# PGTNX01_teensy.net
KiCad netlist of a schematic drawn in EAGLE
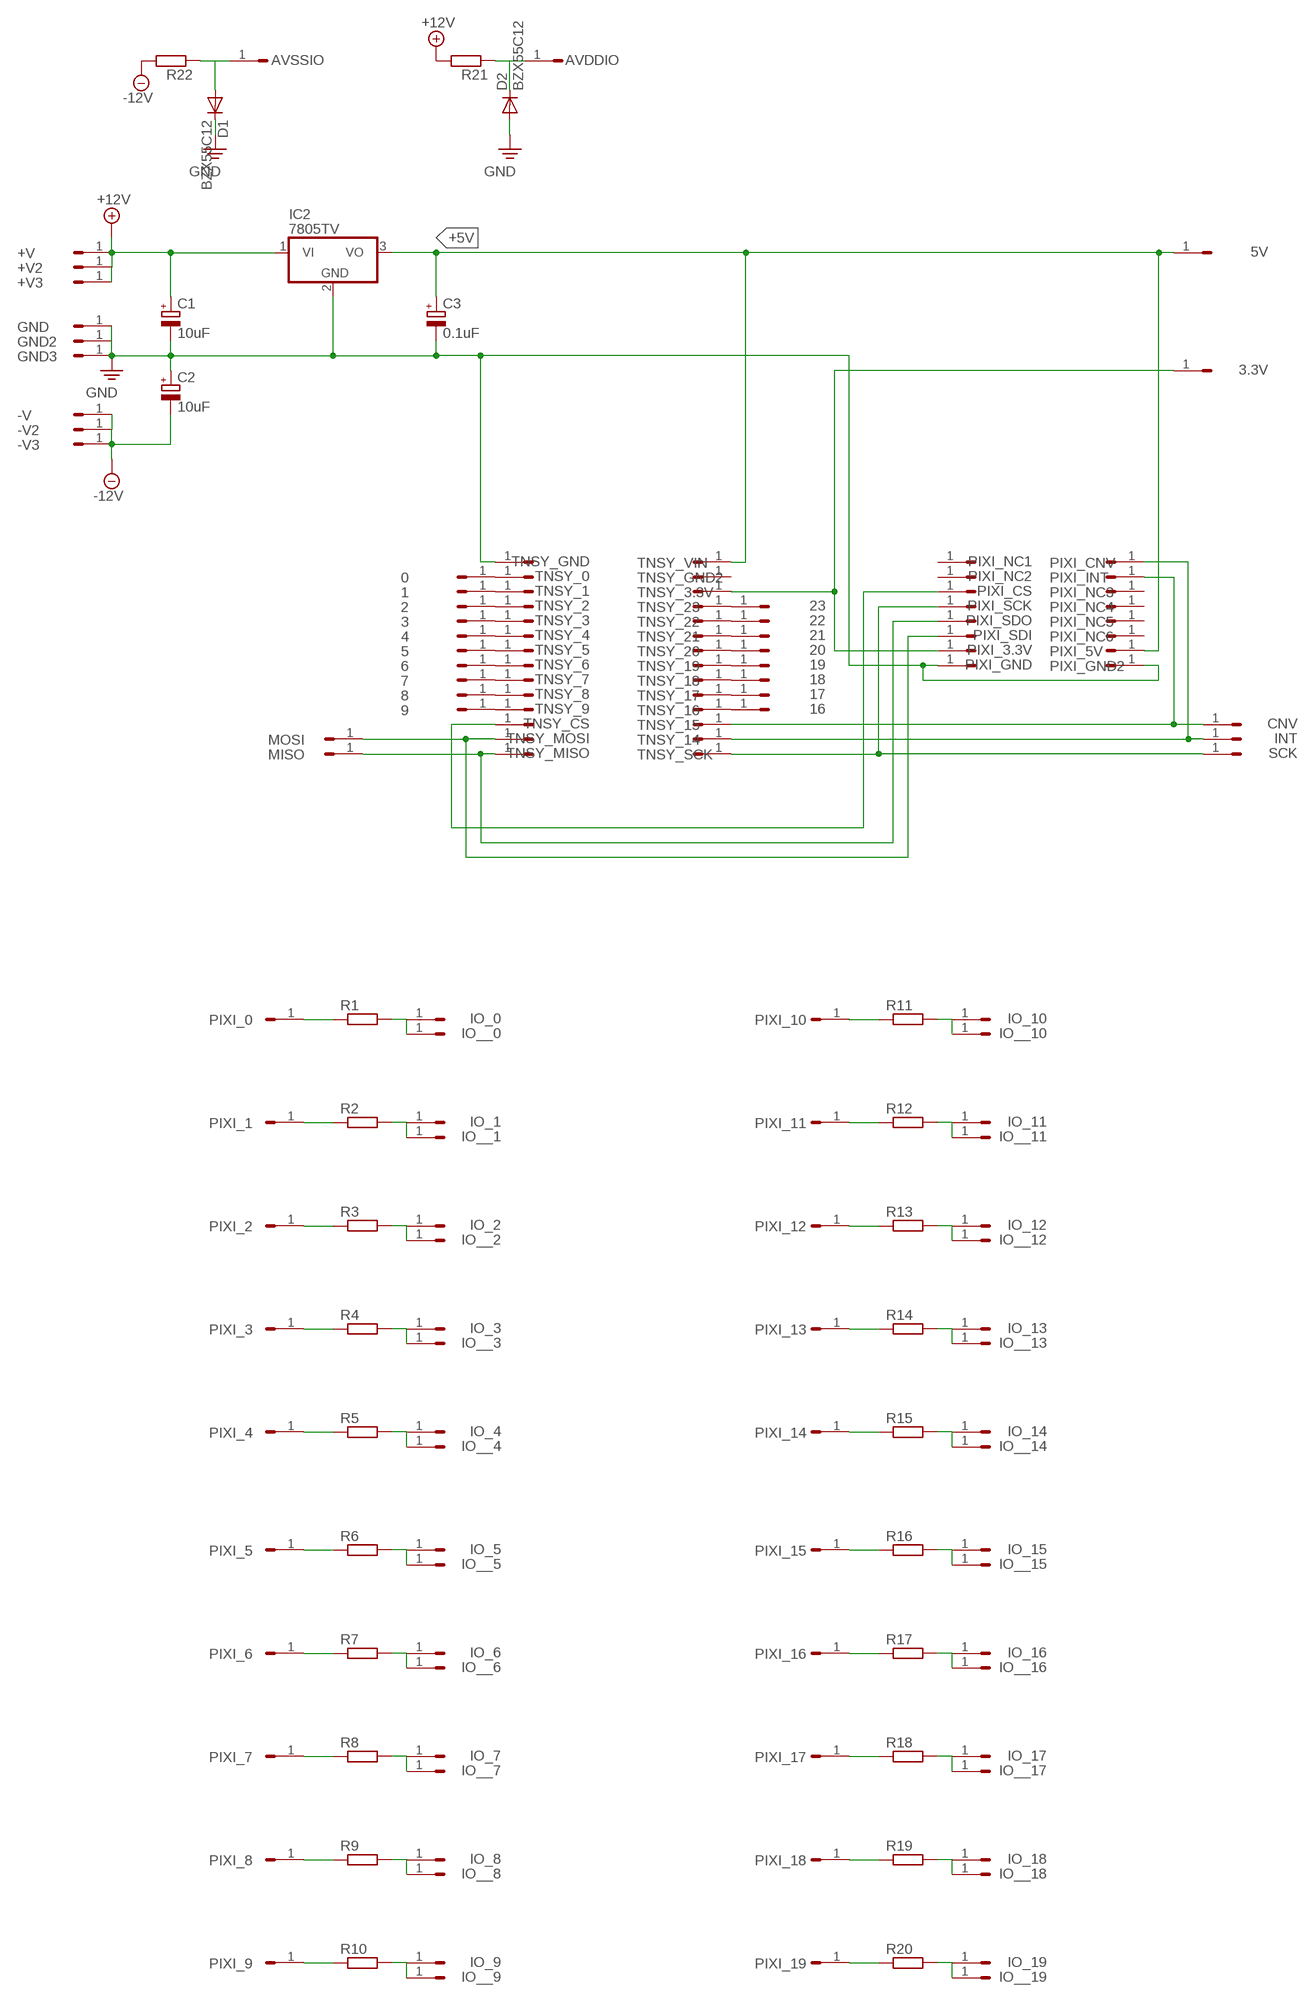
[diagram p0: schematic, sheet 1]

(export (version "E")
  (design (tool "Eeschema 10.0.6"))
  (components
    (comp (ref "+V")
      (value "HEADER/MALE/01")
      (footprint "eagle-import:HEADER_MALE_01")
      (fields (field (name "SPICEPREFIX") "X"))
      (libsource (lib "eagle-import") (part "HEADER/MALE/01"))
    )
    (comp (ref "+V2")
      (value "HEADER/MALE/01")
      (footprint "eagle-import:HEADER_MALE_01")
      (fields (field (name "SPICEPREFIX") "X"))
      (libsource (lib "eagle-import") (part "HEADER/MALE/01"))
    )
    (comp (ref "+V3")
      (value "HEADER/MALE/01")
      (footprint "eagle-import:HEADER_MALE_01")
      (fields (field (name "SPICEPREFIX") "X"))
      (libsource (lib "eagle-import") (part "HEADER/MALE/01"))
    )
    (comp (ref "-V")
      (value "HEADER/MALE/01")
      (footprint "eagle-import:HEADER_MALE_01")
      (fields (field (name "SPICEPREFIX") "X"))
      (libsource (lib "eagle-import") (part "HEADER/MALE/01"))
    )
    (comp (ref "-V2")
      (value "HEADER/MALE/01")
      (footprint "eagle-import:HEADER_MALE_01")
      (fields (field (name "SPICEPREFIX") "X"))
      (libsource (lib "eagle-import") (part "HEADER/MALE/01"))
    )
    (comp (ref "-V3")
      (value "HEADER/MALE/01")
      (footprint "eagle-import:HEADER_MALE_01")
      (fields (field (name "SPICEPREFIX") "X"))
      (libsource (lib "eagle-import") (part "HEADER/MALE/01"))
    )
    (comp (ref "0")
      (value "HEADER/MALE/01")
      (footprint "eagle-import:HEADER_MALE_01")
      (fields (field (name "SPICEPREFIX") "X"))
      (libsource (lib "eagle-import") (part "HEADER/MALE/01"))
    )
    (comp (ref "1")
      (value "HEADER/MALE/01")
      (footprint "eagle-import:HEADER_MALE_01")
      (fields (field (name "SPICEPREFIX") "X"))
      (libsource (lib "eagle-import") (part "HEADER/MALE/01"))
    )
    (comp (ref "2")
      (value "HEADER/MALE/01")
      (footprint "eagle-import:HEADER_MALE_01")
      (fields (field (name "SPICEPREFIX") "X"))
      (libsource (lib "eagle-import") (part "HEADER/MALE/01"))
    )
    (comp (ref "3")
      (value "HEADER/MALE/01")
      (footprint "eagle-import:HEADER_MALE_01")
      (fields (field (name "SPICEPREFIX") "X"))
      (libsource (lib "eagle-import") (part "HEADER/MALE/01"))
    )
    (comp (ref "3.3V")
      (value "HEADER/MALE/01")
      (footprint "eagle-import:HEADER_MALE_01")
      (fields (field (name "SPICEPREFIX") "X"))
      (libsource (lib "eagle-import") (part "HEADER/MALE/01"))
    )
    (comp (ref "4")
      (value "HEADER/MALE/01")
      (footprint "eagle-import:HEADER_MALE_01")
      (fields (field (name "SPICEPREFIX") "X"))
      (libsource (lib "eagle-import") (part "HEADER/MALE/01"))
    )
    (comp (ref "5")
      (value "HEADER/MALE/01")
      (footprint "eagle-import:HEADER_MALE_01")
      (fields (field (name "SPICEPREFIX") "X"))
      (libsource (lib "eagle-import") (part "HEADER/MALE/01"))
    )
    (comp (ref "5V")
      (value "HEADER/MALE/01")
      (footprint "eagle-import:HEADER_MALE_01")
      (fields (field (name "SPICEPREFIX") "X"))
      (libsource (lib "eagle-import") (part "HEADER/MALE/01"))
    )
    (comp (ref "6")
      (value "HEADER/MALE/01")
      (footprint "eagle-import:HEADER_MALE_01")
      (fields (field (name "SPICEPREFIX") "X"))
      (libsource (lib "eagle-import") (part "HEADER/MALE/01"))
    )
    (comp (ref "7")
      (value "HEADER/MALE/01")
      (footprint "eagle-import:HEADER_MALE_01")
      (fields (field (name "SPICEPREFIX") "X"))
      (libsource (lib "eagle-import") (part "HEADER/MALE/01"))
    )
    (comp (ref "8")
      (value "HEADER/MALE/01")
      (footprint "eagle-import:HEADER_MALE_01")
      (fields (field (name "SPICEPREFIX") "X"))
      (libsource (lib "eagle-import") (part "HEADER/MALE/01"))
    )
    (comp (ref "9")
      (value "HEADER/MALE/01")
      (footprint "eagle-import:HEADER_MALE_01")
      (fields (field (name "SPICEPREFIX") "X"))
      (libsource (lib "eagle-import") (part "HEADER/MALE/01"))
    )
    (comp (ref "16")
      (value "HEADER/MALE/01")
      (footprint "eagle-import:HEADER_MALE_01")
      (fields (field (name "SPICEPREFIX") "X"))
      (libsource (lib "eagle-import") (part "HEADER/MALE/01"))
    )
    (comp (ref "17")
      (value "HEADER/MALE/01")
      (footprint "eagle-import:HEADER_MALE_01")
      (fields (field (name "SPICEPREFIX") "X"))
      (libsource (lib "eagle-import") (part "HEADER/MALE/01"))
    )
    (comp (ref "18")
      (value "HEADER/MALE/01")
      (footprint "eagle-import:HEADER_MALE_01")
      (fields (field (name "SPICEPREFIX") "X"))
      (libsource (lib "eagle-import") (part "HEADER/MALE/01"))
    )
    (comp (ref "19")
      (value "HEADER/MALE/01")
      (footprint "eagle-import:HEADER_MALE_01")
      (fields (field (name "SPICEPREFIX") "X"))
      (libsource (lib "eagle-import") (part "HEADER/MALE/01"))
    )
    (comp (ref "20")
      (value "HEADER/MALE/01")
      (footprint "eagle-import:HEADER_MALE_01")
      (fields (field (name "SPICEPREFIX") "X"))
      (libsource (lib "eagle-import") (part "HEADER/MALE/01"))
    )
    (comp (ref "21")
      (value "HEADER/MALE/01")
      (footprint "eagle-import:HEADER_MALE_01")
      (fields (field (name "SPICEPREFIX") "X"))
      (libsource (lib "eagle-import") (part "HEADER/MALE/01"))
    )
    (comp (ref "22")
      (value "HEADER/MALE/01")
      (footprint "eagle-import:HEADER_MALE_01")
      (fields (field (name "SPICEPREFIX") "X"))
      (libsource (lib "eagle-import") (part "HEADER/MALE/01"))
    )
    (comp (ref "23")
      (value "HEADER/MALE/01")
      (footprint "eagle-import:HEADER_MALE_01")
      (fields (field (name "SPICEPREFIX") "X"))
      (libsource (lib "eagle-import") (part "HEADER/MALE/01"))
    )
    (comp (ref "AVDDIO")
      (value "HEADER/MALE/01")
      (footprint "eagle-import:HEADER_MALE_01")
      (fields (field (name "SPICEPREFIX") "X"))
      (libsource (lib "eagle-import") (part "HEADER/MALE/01"))
    )
    (comp (ref "AVSSIO")
      (value "HEADER/MALE/01")
      (footprint "eagle-import:HEADER_MALE_01")
      (fields (field (name "SPICEPREFIX") "X"))
      (libsource (lib "eagle-import") (part "HEADER/MALE/01"))
    )
    (comp (ref "C1")
      (value "10uF")
      (footprint "eagle-import:E2,5-6")
      (fields (field (name "SPICEPREFIX") "C"))
      (libsource (lib "eagle-import") (part "CAPACITOR/POLARIZEDE2.5-6"))
    )
    (comp (ref "C2")
      (value "10uF")
      (footprint "eagle-import:E2,5-6")
      (fields (field (name "SPICEPREFIX") "C"))
      (libsource (lib "eagle-import") (part "CAPACITOR/POLARIZEDE2.5-6"))
    )
    (comp (ref "C3")
      (value "0.1uF")
      (footprint "eagle-import:E2,5-6")
      (fields (field (name "SPICEPREFIX") "C"))
      (libsource (lib "eagle-import") (part "CAPACITOR/POLARIZEDE2.5-6"))
    )
    (comp (ref "CNV")
      (value "HEADER/MALE/01")
      (footprint "eagle-import:HEADER_MALE_01")
      (fields (field (name "SPICEPREFIX") "X"))
      (libsource (lib "eagle-import") (part "HEADER/MALE/01"))
    )
    (comp (ref "D1")
      (value "BZX55C12")
      (footprint "eagle-import:DO35-7")
      (libsource (lib "eagle-import") (part "1N4148DO35-7"))
    )
    (comp (ref "D2")
      (value "BZX55C12")
      (footprint "eagle-import:DO35-7")
      (libsource (lib "eagle-import") (part "1N4148DO35-7"))
    )
    (comp (ref "GND")
      (value "HEADER/MALE/01")
      (footprint "eagle-import:HEADER_MALE_01")
      (fields (field (name "SPICEPREFIX") "X"))
      (libsource (lib "eagle-import") (part "HEADER/MALE/01"))
    )
    (comp (ref "GND2")
      (value "HEADER/MALE/01")
      (footprint "eagle-import:HEADER_MALE_01")
      (fields (field (name "SPICEPREFIX") "X"))
      (libsource (lib "eagle-import") (part "HEADER/MALE/01"))
    )
    (comp (ref "GND3")
      (value "HEADER/MALE/01")
      (footprint "eagle-import:HEADER_MALE_01")
      (fields (field (name "SPICEPREFIX") "X"))
      (libsource (lib "eagle-import") (part "HEADER/MALE/01"))
    )
    (comp (ref "IC2")
      (value "7805TV")
      (footprint "eagle-import:TO220V")
      (libsource (lib "eagle-import") (part "78TV05"))
    )
    (comp (ref "INT")
      (value "HEADER/MALE/01")
      (footprint "eagle-import:HEADER_MALE_01")
      (fields (field (name "SPICEPREFIX") "X"))
      (libsource (lib "eagle-import") (part "HEADER/MALE/01"))
    )
    (comp (ref "IO_0")
      (value "HEADER/MALE/01")
      (footprint "eagle-import:HEADER_MALE_01")
      (fields (field (name "SPICEPREFIX") "X"))
      (libsource (lib "eagle-import") (part "HEADER/MALE/01"))
    )
    (comp (ref "IO_1")
      (value "HEADER/MALE/01")
      (footprint "eagle-import:HEADER_MALE_01")
      (fields (field (name "SPICEPREFIX") "X"))
      (libsource (lib "eagle-import") (part "HEADER/MALE/01"))
    )
    (comp (ref "IO_2")
      (value "HEADER/MALE/01")
      (footprint "eagle-import:HEADER_MALE_01")
      (fields (field (name "SPICEPREFIX") "X"))
      (libsource (lib "eagle-import") (part "HEADER/MALE/01"))
    )
    (comp (ref "IO_3")
      (value "HEADER/MALE/01")
      (footprint "eagle-import:HEADER_MALE_01")
      (fields (field (name "SPICEPREFIX") "X"))
      (libsource (lib "eagle-import") (part "HEADER/MALE/01"))
    )
    (comp (ref "IO_4")
      (value "HEADER/MALE/01")
      (footprint "eagle-import:HEADER_MALE_01")
      (fields (field (name "SPICEPREFIX") "X"))
      (libsource (lib "eagle-import") (part "HEADER/MALE/01"))
    )
    (comp (ref "IO_5")
      (value "HEADER/MALE/01")
      (footprint "eagle-import:HEADER_MALE_01")
      (fields (field (name "SPICEPREFIX") "X"))
      (libsource (lib "eagle-import") (part "HEADER/MALE/01"))
    )
    (comp (ref "IO_6")
      (value "HEADER/MALE/01")
      (footprint "eagle-import:HEADER_MALE_01")
      (fields (field (name "SPICEPREFIX") "X"))
      (libsource (lib "eagle-import") (part "HEADER/MALE/01"))
    )
    (comp (ref "IO_7")
      (value "HEADER/MALE/01")
      (footprint "eagle-import:HEADER_MALE_01")
      (fields (field (name "SPICEPREFIX") "X"))
      (libsource (lib "eagle-import") (part "HEADER/MALE/01"))
    )
    (comp (ref "IO_8")
      (value "HEADER/MALE/01")
      (footprint "eagle-import:HEADER_MALE_01")
      (fields (field (name "SPICEPREFIX") "X"))
      (libsource (lib "eagle-import") (part "HEADER/MALE/01"))
    )
    (comp (ref "IO_9")
      (value "HEADER/MALE/01")
      (footprint "eagle-import:HEADER_MALE_01")
      (fields (field (name "SPICEPREFIX") "X"))
      (libsource (lib "eagle-import") (part "HEADER/MALE/01"))
    )
    (comp (ref "IO_10")
      (value "HEADER/MALE/01")
      (footprint "eagle-import:HEADER_MALE_01")
      (fields (field (name "SPICEPREFIX") "X"))
      (libsource (lib "eagle-import") (part "HEADER/MALE/01"))
    )
    (comp (ref "IO_11")
      (value "HEADER/MALE/01")
      (footprint "eagle-import:HEADER_MALE_01")
      (fields (field (name "SPICEPREFIX") "X"))
      (libsource (lib "eagle-import") (part "HEADER/MALE/01"))
    )
    (comp (ref "IO_12")
      (value "HEADER/MALE/01")
      (footprint "eagle-import:HEADER_MALE_01")
      (fields (field (name "SPICEPREFIX") "X"))
      (libsource (lib "eagle-import") (part "HEADER/MALE/01"))
    )
    (comp (ref "IO_13")
      (value "HEADER/MALE/01")
      (footprint "eagle-import:HEADER_MALE_01")
      (fields (field (name "SPICEPREFIX") "X"))
      (libsource (lib "eagle-import") (part "HEADER/MALE/01"))
    )
    (comp (ref "IO_14")
      (value "HEADER/MALE/01")
      (footprint "eagle-import:HEADER_MALE_01")
      (fields (field (name "SPICEPREFIX") "X"))
      (libsource (lib "eagle-import") (part "HEADER/MALE/01"))
    )
    (comp (ref "IO_15")
      (value "HEADER/MALE/01")
      (footprint "eagle-import:HEADER_MALE_01")
      (fields (field (name "SPICEPREFIX") "X"))
      (libsource (lib "eagle-import") (part "HEADER/MALE/01"))
    )
    (comp (ref "IO_16")
      (value "HEADER/MALE/01")
      (footprint "eagle-import:HEADER_MALE_01")
      (fields (field (name "SPICEPREFIX") "X"))
      (libsource (lib "eagle-import") (part "HEADER/MALE/01"))
    )
    (comp (ref "IO_17")
      (value "HEADER/MALE/01")
      (footprint "eagle-import:HEADER_MALE_01")
      (fields (field (name "SPICEPREFIX") "X"))
      (libsource (lib "eagle-import") (part "HEADER/MALE/01"))
    )
    (comp (ref "IO_18")
      (value "HEADER/MALE/01")
      (footprint "eagle-import:HEADER_MALE_01")
      (fields (field (name "SPICEPREFIX") "X"))
      (libsource (lib "eagle-import") (part "HEADER/MALE/01"))
    )
    (comp (ref "IO_19")
      (value "HEADER/MALE/01")
      (footprint "eagle-import:HEADER_MALE_01")
      (fields (field (name "SPICEPREFIX") "X"))
      (libsource (lib "eagle-import") (part "HEADER/MALE/01"))
    )
    (comp (ref "IO__0")
      (value "HEADER/MALE/01")
      (footprint "eagle-import:HEADER_MALE_01")
      (fields (field (name "SPICEPREFIX") "X"))
      (libsource (lib "eagle-import") (part "HEADER/MALE/01"))
    )
    (comp (ref "IO__1")
      (value "HEADER/MALE/01")
      (footprint "eagle-import:HEADER_MALE_01")
      (fields (field (name "SPICEPREFIX") "X"))
      (libsource (lib "eagle-import") (part "HEADER/MALE/01"))
    )
    (comp (ref "IO__2")
      (value "HEADER/MALE/01")
      (footprint "eagle-import:HEADER_MALE_01")
      (fields (field (name "SPICEPREFIX") "X"))
      (libsource (lib "eagle-import") (part "HEADER/MALE/01"))
    )
    (comp (ref "IO__3")
      (value "HEADER/MALE/01")
      (footprint "eagle-import:HEADER_MALE_01")
      (fields (field (name "SPICEPREFIX") "X"))
      (libsource (lib "eagle-import") (part "HEADER/MALE/01"))
    )
    (comp (ref "IO__4")
      (value "HEADER/MALE/01")
      (footprint "eagle-import:HEADER_MALE_01")
      (fields (field (name "SPICEPREFIX") "X"))
      (libsource (lib "eagle-import") (part "HEADER/MALE/01"))
    )
    (comp (ref "IO__5")
      (value "HEADER/MALE/01")
      (footprint "eagle-import:HEADER_MALE_01")
      (fields (field (name "SPICEPREFIX") "X"))
      (libsource (lib "eagle-import") (part "HEADER/MALE/01"))
    )
    (comp (ref "IO__6")
      (value "HEADER/MALE/01")
      (footprint "eagle-import:HEADER_MALE_01")
      (fields (field (name "SPICEPREFIX") "X"))
      (libsource (lib "eagle-import") (part "HEADER/MALE/01"))
    )
    (comp (ref "IO__7")
      (value "HEADER/MALE/01")
      (footprint "eagle-import:HEADER_MALE_01")
      (fields (field (name "SPICEPREFIX") "X"))
      (libsource (lib "eagle-import") (part "HEADER/MALE/01"))
    )
    (comp (ref "IO__8")
      (value "HEADER/MALE/01")
      (footprint "eagle-import:HEADER_MALE_01")
      (fields (field (name "SPICEPREFIX") "X"))
      (libsource (lib "eagle-import") (part "HEADER/MALE/01"))
    )
    (comp (ref "IO__9")
      (value "HEADER/MALE/01")
      (footprint "eagle-import:HEADER_MALE_01")
      (fields (field (name "SPICEPREFIX") "X"))
      (libsource (lib "eagle-import") (part "HEADER/MALE/01"))
    )
    (comp (ref "IO__10")
      (value "HEADER/MALE/01")
      (footprint "eagle-import:HEADER_MALE_01")
      (fields (field (name "SPICEPREFIX") "X"))
      (libsource (lib "eagle-import") (part "HEADER/MALE/01"))
    )
    (comp (ref "IO__11")
      (value "HEADER/MALE/01")
      (footprint "eagle-import:HEADER_MALE_01")
      (fields (field (name "SPICEPREFIX") "X"))
      (libsource (lib "eagle-import") (part "HEADER/MALE/01"))
    )
    (comp (ref "IO__12")
      (value "HEADER/MALE/01")
      (footprint "eagle-import:HEADER_MALE_01")
      (fields (field (name "SPICEPREFIX") "X"))
      (libsource (lib "eagle-import") (part "HEADER/MALE/01"))
    )
    (comp (ref "IO__13")
      (value "HEADER/MALE/01")
      (footprint "eagle-import:HEADER_MALE_01")
      (fields (field (name "SPICEPREFIX") "X"))
      (libsource (lib "eagle-import") (part "HEADER/MALE/01"))
    )
    (comp (ref "IO__14")
      (value "HEADER/MALE/01")
      (footprint "eagle-import:HEADER_MALE_01")
      (fields (field (name "SPICEPREFIX") "X"))
      (libsource (lib "eagle-import") (part "HEADER/MALE/01"))
    )
    (comp (ref "IO__15")
      (value "HEADER/MALE/01")
      (footprint "eagle-import:HEADER_MALE_01")
      (fields (field (name "SPICEPREFIX") "X"))
      (libsource (lib "eagle-import") (part "HEADER/MALE/01"))
    )
    (comp (ref "IO__16")
      (value "HEADER/MALE/01")
      (footprint "eagle-import:HEADER_MALE_01")
      (fields (field (name "SPICEPREFIX") "X"))
      (libsource (lib "eagle-import") (part "HEADER/MALE/01"))
    )
    (comp (ref "IO__17")
      (value "HEADER/MALE/01")
      (footprint "eagle-import:HEADER_MALE_01")
      (fields (field (name "SPICEPREFIX") "X"))
      (libsource (lib "eagle-import") (part "HEADER/MALE/01"))
    )
    (comp (ref "IO__18")
      (value "HEADER/MALE/01")
      (footprint "eagle-import:HEADER_MALE_01")
      (fields (field (name "SPICEPREFIX") "X"))
      (libsource (lib "eagle-import") (part "HEADER/MALE/01"))
    )
    (comp (ref "IO__19")
      (value "HEADER/MALE/01")
      (footprint "eagle-import:HEADER_MALE_01")
      (fields (field (name "SPICEPREFIX") "X"))
      (libsource (lib "eagle-import") (part "HEADER/MALE/01"))
    )
    (comp (ref "MISO")
      (value "HEADER/MALE/01")
      (footprint "eagle-import:HEADER_MALE_01")
      (fields (field (name "SPICEPREFIX") "X"))
      (libsource (lib "eagle-import") (part "HEADER/MALE/01"))
    )
    (comp (ref "MOSI")
      (value "HEADER/MALE/01")
      (footprint "eagle-import:HEADER_MALE_01")
      (fields (field (name "SPICEPREFIX") "X"))
      (libsource (lib "eagle-import") (part "HEADER/MALE/01"))
    )
    (comp (ref "PIXI_0")
      (value "HEADER/MALE/01")
      (footprint "eagle-import:HEADER_MALE_01")
      (fields (field (name "SPICEPREFIX") "X"))
      (libsource (lib "eagle-import") (part "HEADER/MALE/01"))
    )
    (comp (ref "PIXI_1")
      (value "HEADER/MALE/01")
      (footprint "eagle-import:HEADER_MALE_01")
      (fields (field (name "SPICEPREFIX") "X"))
      (libsource (lib "eagle-import") (part "HEADER/MALE/01"))
    )
    (comp (ref "PIXI_2")
      (value "HEADER/MALE/01")
      (footprint "eagle-import:HEADER_MALE_01")
      (fields (field (name "SPICEPREFIX") "X"))
      (libsource (lib "eagle-import") (part "HEADER/MALE/01"))
    )
    (comp (ref "PIXI_3")
      (value "HEADER/MALE/01")
      (footprint "eagle-import:HEADER_MALE_01")
      (fields (field (name "SPICEPREFIX") "X"))
      (libsource (lib "eagle-import") (part "HEADER/MALE/01"))
    )
    (comp (ref "PIXI_3.3V")
      (value "HEADER/MALE/01")
      (footprint "eagle-import:HEADER_MALE_01")
      (fields (field (name "SPICEPREFIX") "X"))
      (libsource (lib "eagle-import") (part "HEADER/MALE/01"))
    )
    (comp (ref "PIXI_4")
      (value "HEADER/MALE/01")
      (footprint "eagle-import:HEADER_MALE_01")
      (fields (field (name "SPICEPREFIX") "X"))
      (libsource (lib "eagle-import") (part "HEADER/MALE/01"))
    )
    (comp (ref "PIXI_5")
      (value "HEADER/MALE/01")
      (footprint "eagle-import:HEADER_MALE_01")
      (fields (field (name "SPICEPREFIX") "X"))
      (libsource (lib "eagle-import") (part "HEADER/MALE/01"))
    )
    (comp (ref "PIXI_5V")
      (value "HEADER/MALE/01")
      (footprint "eagle-import:HEADER_MALE_01")
      (fields (field (name "SPICEPREFIX") "X"))
      (libsource (lib "eagle-import") (part "HEADER/MALE/01"))
    )
    (comp (ref "PIXI_6")
      (value "HEADER/MALE/01")
      (footprint "eagle-import:HEADER_MALE_01")
      (fields (field (name "SPICEPREFIX") "X"))
      (libsource (lib "eagle-import") (part "HEADER/MALE/01"))
    )
    (comp (ref "PIXI_7")
      (value "HEADER/MALE/01")
      (footprint "eagle-import:HEADER_MALE_01")
      (fields (field (name "SPICEPREFIX") "X"))
      (libsource (lib "eagle-import") (part "HEADER/MALE/01"))
    )
    (comp (ref "PIXI_8")
      (value "HEADER/MALE/01")
      (footprint "eagle-import:HEADER_MALE_01")
      (fields (field (name "SPICEPREFIX") "X"))
      (libsource (lib "eagle-import") (part "HEADER/MALE/01"))
    )
    (comp (ref "PIXI_9")
      (value "HEADER/MALE/01")
      (footprint "eagle-import:HEADER_MALE_01")
      (fields (field (name "SPICEPREFIX") "X"))
      (libsource (lib "eagle-import") (part "HEADER/MALE/01"))
    )
    (comp (ref "PIXI_10")
      (value "HEADER/MALE/01")
      (footprint "eagle-import:HEADER_MALE_01")
      (fields (field (name "SPICEPREFIX") "X"))
      (libsource (lib "eagle-import") (part "HEADER/MALE/01"))
    )
    (comp (ref "PIXI_11")
      (value "HEADER/MALE/01")
      (footprint "eagle-import:HEADER_MALE_01")
      (fields (field (name "SPICEPREFIX") "X"))
      (libsource (lib "eagle-import") (part "HEADER/MALE/01"))
    )
    (comp (ref "PIXI_12")
      (value "HEADER/MALE/01")
      (footprint "eagle-import:HEADER_MALE_01")
      (fields (field (name "SPICEPREFIX") "X"))
      (libsource (lib "eagle-import") (part "HEADER/MALE/01"))
    )
    (comp (ref "PIXI_13")
      (value "HEADER/MALE/01")
      (footprint "eagle-import:HEADER_MALE_01")
      (fields (field (name "SPICEPREFIX") "X"))
      (libsource (lib "eagle-import") (part "HEADER/MALE/01"))
    )
    (comp (ref "PIXI_14")
      (value "HEADER/MALE/01")
      (footprint "eagle-import:HEADER_MALE_01")
      (fields (field (name "SPICEPREFIX") "X"))
      (libsource (lib "eagle-import") (part "HEADER/MALE/01"))
    )
    (comp (ref "PIXI_15")
      (value "HEADER/MALE/01")
      (footprint "eagle-import:HEADER_MALE_01")
      (fields (field (name "SPICEPREFIX") "X"))
      (libsource (lib "eagle-import") (part "HEADER/MALE/01"))
    )
    (comp (ref "PIXI_16")
      (value "HEADER/MALE/01")
      (footprint "eagle-import:HEADER_MALE_01")
      (fields (field (name "SPICEPREFIX") "X"))
      (libsource (lib "eagle-import") (part "HEADER/MALE/01"))
    )
    (comp (ref "PIXI_17")
      (value "HEADER/MALE/01")
      (footprint "eagle-import:HEADER_MALE_01")
      (fields (field (name "SPICEPREFIX") "X"))
      (libsource (lib "eagle-import") (part "HEADER/MALE/01"))
    )
    (comp (ref "PIXI_18")
      (value "HEADER/MALE/01")
      (footprint "eagle-import:HEADER_MALE_01")
      (fields (field (name "SPICEPREFIX") "X"))
      (libsource (lib "eagle-import") (part "HEADER/MALE/01"))
    )
    (comp (ref "PIXI_19")
      (value "HEADER/MALE/01")
      (footprint "eagle-import:HEADER_MALE_01")
      (fields (field (name "SPICEPREFIX") "X"))
      (libsource (lib "eagle-import") (part "HEADER/MALE/01"))
    )
    (comp (ref "PIXI_CNV")
      (value "HEADER/MALE/01")
      (footprint "eagle-import:HEADER_MALE_01")
      (fields (field (name "SPICEPREFIX") "X"))
      (libsource (lib "eagle-import") (part "HEADER/MALE/01"))
    )
    (comp (ref "PIXI_CS")
      (value "HEADER/MALE/01")
      (footprint "eagle-import:HEADER_MALE_01")
      (fields (field (name "SPICEPREFIX") "X"))
      (libsource (lib "eagle-import") (part "HEADER/MALE/01"))
    )
    (comp (ref "PIXI_GND")
      (value "HEADER/MALE/01")
      (footprint "eagle-import:HEADER_MALE_01")
      (fields (field (name "SPICEPREFIX") "X"))
      (libsource (lib "eagle-import") (part "HEADER/MALE/01"))
    )
    (comp (ref "PIXI_GND2")
      (value "HEADER/MALE/01")
      (footprint "eagle-import:HEADER_MALE_01")
      (fields (field (name "SPICEPREFIX") "X"))
      (libsource (lib "eagle-import") (part "HEADER/MALE/01"))
    )
    (comp (ref "PIXI_INT")
      (value "HEADER/MALE/01")
      (footprint "eagle-import:HEADER_MALE_01")
      (fields (field (name "SPICEPREFIX") "X"))
      (libsource (lib "eagle-import") (part "HEADER/MALE/01"))
    )
    (comp (ref "PIXI_NC1")
      (value "HEADER/MALE/01")
      (footprint "eagle-import:HEADER_MALE_01")
      (fields (field (name "SPICEPREFIX") "X"))
      (libsource (lib "eagle-import") (part "HEADER/MALE/01"))
    )
    (comp (ref "PIXI_NC2")
      (value "HEADER/MALE/01")
      (footprint "eagle-import:HEADER_MALE_01")
      (fields (field (name "SPICEPREFIX") "X"))
      (libsource (lib "eagle-import") (part "HEADER/MALE/01"))
    )
    (comp (ref "PIXI_NC3")
      (value "HEADER/MALE/01")
      (footprint "eagle-import:HEADER_MALE_01")
      (fields (field (name "SPICEPREFIX") "X"))
      (libsource (lib "eagle-import") (part "HEADER/MALE/01"))
    )
    (comp (ref "PIXI_NC4")
      (value "HEADER/MALE/01")
      (footprint "eagle-import:HEADER_MALE_01")
      (fields (field (name "SPICEPREFIX") "X"))
      (libsource (lib "eagle-import") (part "HEADER/MALE/01"))
    )
    (comp (ref "PIXI_NC5")
      (value "HEADER/MALE/01")
      (footprint "eagle-import:HEADER_MALE_01")
      (fields (field (name "SPICEPREFIX") "X"))
      (libsource (lib "eagle-import") (part "HEADER/MALE/01"))
    )
    (comp (ref "PIXI_NC6")
      (value "HEADER/MALE/01")
      (footprint "eagle-import:HEADER_MALE_01")
      (fields (field (name "SPICEPREFIX") "X"))
      (libsource (lib "eagle-import") (part "HEADER/MALE/01"))
    )
    (comp (ref "PIXI_SCK")
      (value "HEADER/MALE/01")
      (footprint "eagle-import:HEADER_MALE_01")
      (fields (field (name "SPICEPREFIX") "X"))
      (libsource (lib "eagle-import") (part "HEADER/MALE/01"))
    )
    (comp (ref "PIXI_SDI")
      (value "HEADER/MALE/01")
      (footprint "eagle-import:HEADER_MALE_01")
      (fields (field (name "SPICEPREFIX") "X"))
      (libsource (lib "eagle-import") (part "HEADER/MALE/01"))
    )
    (comp (ref "PIXI_SDO")
      (value "HEADER/MALE/01")
      (footprint "eagle-import:HEADER_MALE_01")
      (fields (field (name "SPICEPREFIX") "X"))
      (libsource (lib "eagle-import") (part "HEADER/MALE/01"))
    )
    (comp (ref "R1")
      (value "RESISTORRESISTOR/UPRIGHT/7.5")
      (footprint "eagle-import:RESISTOR_7.5")
      (libsource (lib "eagle-import") (part "RESISTORRESISTOR/UPRIGHT/7.5"))
    )
    (comp (ref "R2")
      (value "RESISTORRESISTOR/UPRIGHT/7.5")
      (footprint "eagle-import:RESISTOR_7.5")
      (libsource (lib "eagle-import") (part "RESISTORRESISTOR/UPRIGHT/7.5"))
    )
    (comp (ref "R3")
      (value "RESISTORRESISTOR/UPRIGHT/7.5")
      (footprint "eagle-import:RESISTOR_7.5")
      (libsource (lib "eagle-import") (part "RESISTORRESISTOR/UPRIGHT/7.5"))
    )
    (comp (ref "R4")
      (value "RESISTORRESISTOR/UPRIGHT/7.5")
      (footprint "eagle-import:RESISTOR_7.5")
      (libsource (lib "eagle-import") (part "RESISTORRESISTOR/UPRIGHT/7.5"))
    )
    (comp (ref "R5")
      (value "RESISTORRESISTOR/UPRIGHT/7.5")
      (footprint "eagle-import:RESISTOR_7.5")
      (libsource (lib "eagle-import") (part "RESISTORRESISTOR/UPRIGHT/7.5"))
    )
    (comp (ref "R6")
      (value "RESISTORRESISTOR/UPRIGHT/7.5")
      (footprint "eagle-import:RESISTOR_7.5")
      (libsource (lib "eagle-import") (part "RESISTORRESISTOR/UPRIGHT/7.5"))
    )
    (comp (ref "R7")
      (value "RESISTORRESISTOR/UPRIGHT/7.5")
      (footprint "eagle-import:RESISTOR_7.5")
      (libsource (lib "eagle-import") (part "RESISTORRESISTOR/UPRIGHT/7.5"))
    )
    (comp (ref "R8")
      (value "RESISTORRESISTOR/UPRIGHT/7.5")
      (footprint "eagle-import:RESISTOR_7.5")
      (libsource (lib "eagle-import") (part "RESISTORRESISTOR/UPRIGHT/7.5"))
    )
    (comp (ref "R9")
      (value "RESISTORRESISTOR/UPRIGHT/7.5")
      (footprint "eagle-import:RESISTOR_7.5")
      (libsource (lib "eagle-import") (part "RESISTORRESISTOR/UPRIGHT/7.5"))
    )
    (comp (ref "R10")
      (value "RESISTORRESISTOR/UPRIGHT/7.5")
      (footprint "eagle-import:RESISTOR_7.5")
      (libsource (lib "eagle-import") (part "RESISTORRESISTOR/UPRIGHT/7.5"))
    )
    (comp (ref "R11")
      (value "RESISTORRESISTOR/UPRIGHT/7.5")
      (footprint "eagle-import:RESISTOR_7.5")
      (libsource (lib "eagle-import") (part "RESISTORRESISTOR/UPRIGHT/7.5"))
    )
    (comp (ref "R12")
      (value "RESISTORRESISTOR/UPRIGHT/7.5")
      (footprint "eagle-import:RESISTOR_7.5")
      (libsource (lib "eagle-import") (part "RESISTORRESISTOR/UPRIGHT/7.5"))
    )
    (comp (ref "R13")
      (value "RESISTORRESISTOR/UPRIGHT/7.5")
      (footprint "eagle-import:RESISTOR_7.5")
      (libsource (lib "eagle-import") (part "RESISTORRESISTOR/UPRIGHT/7.5"))
    )
    (comp (ref "R14")
      (value "RESISTORRESISTOR/UPRIGHT/7.5")
      (footprint "eagle-import:RESISTOR_7.5")
      (libsource (lib "eagle-import") (part "RESISTORRESISTOR/UPRIGHT/7.5"))
    )
    (comp (ref "R15")
      (value "RESISTORRESISTOR/UPRIGHT/7.5")
      (footprint "eagle-import:RESISTOR_7.5")
      (libsource (lib "eagle-import") (part "RESISTORRESISTOR/UPRIGHT/7.5"))
    )
    (comp (ref "R16")
      (value "RESISTORRESISTOR/UPRIGHT/7.5")
      (footprint "eagle-import:RESISTOR_7.5")
      (libsource (lib "eagle-import") (part "RESISTORRESISTOR/UPRIGHT/7.5"))
    )
    (comp (ref "R17")
      (value "RESISTORRESISTOR/UPRIGHT/7.5")
      (footprint "eagle-import:RESISTOR_7.5")
      (libsource (lib "eagle-import") (part "RESISTORRESISTOR/UPRIGHT/7.5"))
    )
    (comp (ref "R18")
      (value "RESISTORRESISTOR/UPRIGHT/7.5")
      (footprint "eagle-import:RESISTOR_7.5")
      (libsource (lib "eagle-import") (part "RESISTORRESISTOR/UPRIGHT/7.5"))
    )
    (comp (ref "R19")
      (value "RESISTORRESISTOR/UPRIGHT/7.5")
      (footprint "eagle-import:RESISTOR_7.5")
      (libsource (lib "eagle-import") (part "RESISTORRESISTOR/UPRIGHT/7.5"))
    )
    (comp (ref "R20")
      (value "RESISTORRESISTOR/UPRIGHT/7.5")
      (footprint "eagle-import:RESISTOR_7.5")
      (libsource (lib "eagle-import") (part "RESISTORRESISTOR/UPRIGHT/7.5"))
    )
    (comp (ref "R21")
      (value "RESISTORRESISTOR/UPRIGHT/7.5")
      (footprint "eagle-import:RESISTOR_7.5")
      (libsource (lib "eagle-import") (part "RESISTORRESISTOR/UPRIGHT/7.5"))
    )
    (comp (ref "R22")
      (value "RESISTORRESISTOR/UPRIGHT/7.5")
      (footprint "eagle-import:RESISTOR_7.5")
      (libsource (lib "eagle-import") (part "RESISTORRESISTOR/UPRIGHT/7.5"))
    )
    (comp (ref "SCK")
      (value "HEADER/MALE/01")
      (footprint "eagle-import:HEADER_MALE_01")
      (fields (field (name "SPICEPREFIX") "X"))
      (libsource (lib "eagle-import") (part "HEADER/MALE/01"))
    )
    (comp (ref "TNSY_0")
      (value "HEADER/MALE/01")
      (footprint "eagle-import:HEADER_MALE_01")
      (fields (field (name "SPICEPREFIX") "X"))
      (libsource (lib "eagle-import") (part "HEADER/MALE/01"))
    )
    (comp (ref "TNSY_1")
      (value "HEADER/MALE/01")
      (footprint "eagle-import:HEADER_MALE_01")
      (fields (field (name "SPICEPREFIX") "X"))
      (libsource (lib "eagle-import") (part "HEADER/MALE/01"))
    )
    (comp (ref "TNSY_2")
      (value "HEADER/MALE/01")
      (footprint "eagle-import:HEADER_MALE_01")
      (fields (field (name "SPICEPREFIX") "X"))
      (libsource (lib "eagle-import") (part "HEADER/MALE/01"))
    )
    (comp (ref "TNSY_3")
      (value "HEADER/MALE/01")
      (footprint "eagle-import:HEADER_MALE_01")
      (fields (field (name "SPICEPREFIX") "X"))
      (libsource (lib "eagle-import") (part "HEADER/MALE/01"))
    )
    (comp (ref "TNSY_3.3V")
      (value "HEADER/MALE/01")
      (footprint "eagle-import:HEADER_MALE_01")
      (fields (field (name "SPICEPREFIX") "X"))
      (libsource (lib "eagle-import") (part "HEADER/MALE/01"))
    )
    (comp (ref "TNSY_4")
      (value "HEADER/MALE/01")
      (footprint "eagle-import:HEADER_MALE_01")
      (fields (field (name "SPICEPREFIX") "X"))
      (libsource (lib "eagle-import") (part "HEADER/MALE/01"))
    )
    (comp (ref "TNSY_5")
      (value "HEADER/MALE/01")
      (footprint "eagle-import:HEADER_MALE_01")
      (fields (field (name "SPICEPREFIX") "X"))
      (libsource (lib "eagle-import") (part "HEADER/MALE/01"))
    )
    (comp (ref "TNSY_6")
      (value "HEADER/MALE/01")
      (footprint "eagle-import:HEADER_MALE_01")
      (fields (field (name "SPICEPREFIX") "X"))
      (libsource (lib "eagle-import") (part "HEADER/MALE/01"))
    )
    (comp (ref "TNSY_7")
      (value "HEADER/MALE/01")
      (footprint "eagle-import:HEADER_MALE_01")
      (fields (field (name "SPICEPREFIX") "X"))
      (libsource (lib "eagle-import") (part "HEADER/MALE/01"))
    )
    (comp (ref "TNSY_8")
      (value "HEADER/MALE/01")
      (footprint "eagle-import:HEADER_MALE_01")
      (fields (field (name "SPICEPREFIX") "X"))
      (libsource (lib "eagle-import") (part "HEADER/MALE/01"))
    )
    (comp (ref "TNSY_9")
      (value "HEADER/MALE/01")
      (footprint "eagle-import:HEADER_MALE_01")
      (fields (field (name "SPICEPREFIX") "X"))
      (libsource (lib "eagle-import") (part "HEADER/MALE/01"))
    )
    (comp (ref "TNSY_14")
      (value "HEADER/MALE/01")
      (footprint "eagle-import:HEADER_MALE_01")
      (fields (field (name "SPICEPREFIX") "X"))
      (libsource (lib "eagle-import") (part "HEADER/MALE/01"))
    )
    (comp (ref "TNSY_15")
      (value "HEADER/MALE/01")
      (footprint "eagle-import:HEADER_MALE_01")
      (fields (field (name "SPICEPREFIX") "X"))
      (libsource (lib "eagle-import") (part "HEADER/MALE/01"))
    )
    (comp (ref "TNSY_16")
      (value "HEADER/MALE/01")
      (footprint "eagle-import:HEADER_MALE_01")
      (fields (field (name "SPICEPREFIX") "X"))
      (libsource (lib "eagle-import") (part "HEADER/MALE/01"))
    )
    (comp (ref "TNSY_17")
      (value "HEADER/MALE/01")
      (footprint "eagle-import:HEADER_MALE_01")
      (fields (field (name "SPICEPREFIX") "X"))
      (libsource (lib "eagle-import") (part "HEADER/MALE/01"))
    )
    (comp (ref "TNSY_18")
      (value "HEADER/MALE/01")
      (footprint "eagle-import:HEADER_MALE_01")
      (fields (field (name "SPICEPREFIX") "X"))
      (libsource (lib "eagle-import") (part "HEADER/MALE/01"))
    )
    (comp (ref "TNSY_19")
      (value "HEADER/MALE/01")
      (footprint "eagle-import:HEADER_MALE_01")
      (fields (field (name "SPICEPREFIX") "X"))
      (libsource (lib "eagle-import") (part "HEADER/MALE/01"))
    )
    (comp (ref "TNSY_20")
      (value "HEADER/MALE/01")
      (footprint "eagle-import:HEADER_MALE_01")
      (fields (field (name "SPICEPREFIX") "X"))
      (libsource (lib "eagle-import") (part "HEADER/MALE/01"))
    )
    (comp (ref "TNSY_21")
      (value "HEADER/MALE/01")
      (footprint "eagle-import:HEADER_MALE_01")
      (fields (field (name "SPICEPREFIX") "X"))
      (libsource (lib "eagle-import") (part "HEADER/MALE/01"))
    )
    (comp (ref "TNSY_22")
      (value "HEADER/MALE/01")
      (footprint "eagle-import:HEADER_MALE_01")
      (fields (field (name "SPICEPREFIX") "X"))
      (libsource (lib "eagle-import") (part "HEADER/MALE/01"))
    )
    (comp (ref "TNSY_23")
      (value "HEADER/MALE/01")
      (footprint "eagle-import:HEADER_MALE_01")
      (fields (field (name "SPICEPREFIX") "X"))
      (libsource (lib "eagle-import") (part "HEADER/MALE/01"))
    )
    (comp (ref "TNSY_CS")
      (value "HEADER/MALE/01")
      (footprint "eagle-import:HEADER_MALE_01")
      (fields (field (name "SPICEPREFIX") "X"))
      (libsource (lib "eagle-import") (part "HEADER/MALE/01"))
    )
    (comp (ref "TNSY_GND")
      (value "HEADER/MALE/01")
      (footprint "eagle-import:HEADER_MALE_01")
      (fields (field (name "SPICEPREFIX") "X"))
      (libsource (lib "eagle-import") (part "HEADER/MALE/01"))
    )
    (comp (ref "TNSY_GND2")
      (value "HEADER/MALE/01")
      (footprint "eagle-import:HEADER_MALE_01")
      (fields (field (name "SPICEPREFIX") "X"))
      (libsource (lib "eagle-import") (part "HEADER/MALE/01"))
    )
    (comp (ref "TNSY_MISO")
      (value "HEADER/MALE/01")
      (footprint "eagle-import:HEADER_MALE_01")
      (fields (field (name "SPICEPREFIX") "X"))
      (libsource (lib "eagle-import") (part "HEADER/MALE/01"))
    )
    (comp (ref "TNSY_MOSI")
      (value "HEADER/MALE/01")
      (footprint "eagle-import:HEADER_MALE_01")
      (fields (field (name "SPICEPREFIX") "X"))
      (libsource (lib "eagle-import") (part "HEADER/MALE/01"))
    )
    (comp (ref "TNSY_SCK")
      (value "HEADER/MALE/01")
      (footprint "eagle-import:HEADER_MALE_01")
      (fields (field (name "SPICEPREFIX") "X"))
      (libsource (lib "eagle-import") (part "HEADER/MALE/01"))
    )
    (comp (ref "TNSY_VIN")
      (value "HEADER/MALE/01")
      (footprint "eagle-import:HEADER_MALE_01")
      (fields (field (name "SPICEPREFIX") "X"))
      (libsource (lib "eagle-import") (part "HEADER/MALE/01"))
    )
  )
  (nets
    (net (code "1") (name "+5V") (class "Default")
      (node (ref "5V") (pin "1") (pinfunction "3_1") (pintype "passive"))
      (node (ref "C3") (pin "+") (pinfunction "+_+") (pintype "passive"))
      (node (ref "IC2") (pin "3") (pinfunction "VO_3") (pintype "passive"))
      (node (ref "PIXI_5V") (pin "1") (pinfunction "3_1") (pintype "passive"))
      (node (ref "TNSY_VIN") (pin "1") (pinfunction "3_1") (pintype "passive"))
    )
    (net (code "2") (name "+12V") (class "Default")
      (node (ref "+V") (pin "1") (pinfunction "3_1") (pintype "passive"))
      (node (ref "+V2") (pin "1") (pinfunction "3_1") (pintype "passive"))
      (node (ref "+V3") (pin "1") (pinfunction "3_1") (pintype "passive"))
      (node (ref "C1") (pin "+") (pinfunction "+_+") (pintype "passive"))
      (node (ref "IC2") (pin "1") (pinfunction "VI_1") (pintype "input"))
      (node (ref "R21") (pin "2") (pinfunction "2_2") (pintype "passive"))
    )
    (net (code "3") (name "-12V") (class "Default")
      (node (ref "-V") (pin "1") (pinfunction "3_1") (pintype "passive"))
      (node (ref "-V2") (pin "1") (pinfunction "3_1") (pintype "passive"))
      (node (ref "-V3") (pin "1") (pinfunction "3_1") (pintype "passive"))
      (node (ref "C2") (pin "-") (pinfunction "-_-") (pintype "passive"))
      (node (ref "R22") (pin "2") (pinfunction "2_2") (pintype "passive"))
    )
    (net (code "4") (name "GND") (class "Default")
      (node (ref "C1") (pin "-") (pinfunction "-_-") (pintype "passive"))
      (node (ref "C2") (pin "+") (pinfunction "+_+") (pintype "passive"))
      (node (ref "C3") (pin "-") (pinfunction "-_-") (pintype "passive"))
      (node (ref "D1") (pin "C") (pinfunction "C_C") (pintype "passive"))
      (node (ref "D2") (pin "A") (pinfunction "A_A") (pintype "passive"))
      (node (ref "GND") (pin "1") (pinfunction "3_1") (pintype "passive"))
      (node (ref "GND2") (pin "1") (pinfunction "3_1") (pintype "passive"))
      (node (ref "GND3") (pin "1") (pinfunction "3_1") (pintype "passive"))
      (node (ref "IC2") (pin "2") (pinfunction "GND_2") (pintype "passive"))
      (node (ref "PIXI_GND") (pin "1") (pinfunction "3_1") (pintype "passive"))
      (node (ref "PIXI_GND2") (pin "1") (pinfunction "3_1") (pintype "passive"))
      (node (ref "TNSY_GND") (pin "1") (pinfunction "3_1") (pintype "passive"))
    )
    (net (code "5") (name "Net-(0-3)") (class "Default")
      (node (ref "0") (pin "1") (pinfunction "3_1") (pintype "passive"))
      (node (ref "TNSY_0") (pin "1") (pinfunction "3_1") (pintype "passive"))
    )
    (net (code "6") (name "Net-(1-3)") (class "Default")
      (node (ref "1") (pin "1") (pinfunction "3_1") (pintype "passive"))
      (node (ref "TNSY_1") (pin "1") (pinfunction "3_1") (pintype "passive"))
    )
    (net (code "7") (name "Net-(2-3)") (class "Default")
      (node (ref "2") (pin "1") (pinfunction "3_1") (pintype "passive"))
      (node (ref "TNSY_2") (pin "1") (pinfunction "3_1") (pintype "passive"))
    )
    (net (code "8") (name "Net-(3-3)") (class "Default")
      (node (ref "3") (pin "1") (pinfunction "3_1") (pintype "passive"))
      (node (ref "TNSY_3") (pin "1") (pinfunction "3_1") (pintype "passive"))
    )
    (net (code "9") (name "Net-(3.3V-3)") (class "Default")
      (node (ref "3.3V") (pin "1") (pinfunction "3_1") (pintype "passive"))
      (node (ref "PIXI_3.3V") (pin "1") (pinfunction "3_1") (pintype "passive"))
      (node (ref "TNSY_3.3V") (pin "1") (pinfunction "3_1") (pintype "passive"))
    )
    (net (code "10") (name "Net-(4-3)") (class "Default")
      (node (ref "4") (pin "1") (pinfunction "3_1") (pintype "passive"))
      (node (ref "TNSY_4") (pin "1") (pinfunction "3_1") (pintype "passive"))
    )
    (net (code "11") (name "Net-(5-3)") (class "Default")
      (node (ref "5") (pin "1") (pinfunction "3_1") (pintype "passive"))
      (node (ref "TNSY_5") (pin "1") (pinfunction "3_1") (pintype "passive"))
    )
    (net (code "12") (name "Net-(6-3)") (class "Default")
      (node (ref "6") (pin "1") (pinfunction "3_1") (pintype "passive"))
      (node (ref "TNSY_6") (pin "1") (pinfunction "3_1") (pintype "passive"))
    )
    (net (code "13") (name "Net-(7-3)") (class "Default")
      (node (ref "7") (pin "1") (pinfunction "3_1") (pintype "passive"))
      (node (ref "TNSY_7") (pin "1") (pinfunction "3_1") (pintype "passive"))
    )
    (net (code "14") (name "Net-(8-3)") (class "Default")
      (node (ref "8") (pin "1") (pinfunction "3_1") (pintype "passive"))
      (node (ref "TNSY_8") (pin "1") (pinfunction "3_1") (pintype "passive"))
    )
    (net (code "15") (name "Net-(9-3)") (class "Default")
      (node (ref "9") (pin "1") (pinfunction "3_1") (pintype "passive"))
      (node (ref "TNSY_9") (pin "1") (pinfunction "3_1") (pintype "passive"))
    )
    (net (code "16") (name "Net-(16-3)") (class "Default")
      (node (ref "16") (pin "1") (pinfunction "3_1") (pintype "passive"))
      (node (ref "TNSY_16") (pin "1") (pinfunction "3_1") (pintype "passive"))
    )
    (net (code "17") (name "Net-(17-3)") (class "Default")
      (node (ref "17") (pin "1") (pinfunction "3_1") (pintype "passive"))
      (node (ref "TNSY_17") (pin "1") (pinfunction "3_1") (pintype "passive"))
    )
    (net (code "18") (name "Net-(18-3)") (class "Default")
      (node (ref "18") (pin "1") (pinfunction "3_1") (pintype "passive"))
      (node (ref "TNSY_18") (pin "1") (pinfunction "3_1") (pintype "passive"))
    )
    (net (code "19") (name "Net-(19-3)") (class "Default")
      (node (ref "19") (pin "1") (pinfunction "3_1") (pintype "passive"))
      (node (ref "TNSY_19") (pin "1") (pinfunction "3_1") (pintype "passive"))
    )
    (net (code "20") (name "Net-(20-3)") (class "Default")
      (node (ref "20") (pin "1") (pinfunction "3_1") (pintype "passive"))
      (node (ref "TNSY_20") (pin "1") (pinfunction "3_1") (pintype "passive"))
    )
    (net (code "21") (name "Net-(21-3)") (class "Default")
      (node (ref "21") (pin "1") (pinfunction "3_1") (pintype "passive"))
      (node (ref "TNSY_21") (pin "1") (pinfunction "3_1") (pintype "passive"))
    )
    (net (code "22") (name "Net-(22-3)") (class "Default")
      (node (ref "22") (pin "1") (pinfunction "3_1") (pintype "passive"))
      (node (ref "TNSY_22") (pin "1") (pinfunction "3_1") (pintype "passive"))
    )
    (net (code "23") (name "Net-(23-3)") (class "Default")
      (node (ref "23") (pin "1") (pinfunction "3_1") (pintype "passive"))
      (node (ref "TNSY_23") (pin "1") (pinfunction "3_1") (pintype "passive"))
    )
    (net (code "24") (name "Net-(AVDDIO-3)") (class "Default")
      (node (ref "AVDDIO") (pin "1") (pinfunction "3_1") (pintype "passive"))
      (node (ref "D2") (pin "C") (pinfunction "C_C") (pintype "passive"))
      (node (ref "R21") (pin "1") (pinfunction "1_1") (pintype "passive"))
    )
    (net (code "25") (name "Net-(AVSSIO-3)") (class "Default")
      (node (ref "AVSSIO") (pin "1") (pinfunction "3_1") (pintype "passive"))
      (node (ref "D1") (pin "A") (pinfunction "A_A") (pintype "passive"))
      (node (ref "R22") (pin "1") (pinfunction "1_1") (pintype "passive"))
    )
    (net (code "26") (name "Net-(CNV-3)") (class "Default")
      (node (ref "CNV") (pin "1") (pinfunction "3_1") (pintype "passive"))
      (node (ref "PIXI_INT") (pin "1") (pinfunction "3_1") (pintype "passive"))
      (node (ref "TNSY_15") (pin "1") (pinfunction "3_1") (pintype "passive"))
    )
    (net (code "27") (name "Net-(INT-3)") (class "Default")
      (node (ref "INT") (pin "1") (pinfunction "3_1") (pintype "passive"))
      (node (ref "PIXI_CNV") (pin "1") (pinfunction "3_1") (pintype "passive"))
      (node (ref "TNSY_14") (pin "1") (pinfunction "3_1") (pintype "passive"))
    )
    (net (code "28") (name "Net-(IO_0-3)") (class "Default")
      (node (ref "IO_0") (pin "1") (pinfunction "3_1") (pintype "passive"))
      (node (ref "IO__0") (pin "1") (pinfunction "3_1") (pintype "passive"))
      (node (ref "R1") (pin "2") (pinfunction "2_2") (pintype "passive"))
    )
    (net (code "29") (name "Net-(IO_1-3)") (class "Default")
      (node (ref "IO_1") (pin "1") (pinfunction "3_1") (pintype "passive"))
      (node (ref "IO__1") (pin "1") (pinfunction "3_1") (pintype "passive"))
      (node (ref "R2") (pin "2") (pinfunction "2_2") (pintype "passive"))
    )
    (net (code "30") (name "Net-(IO_2-3)") (class "Default")
      (node (ref "IO_2") (pin "1") (pinfunction "3_1") (pintype "passive"))
      (node (ref "IO__2") (pin "1") (pinfunction "3_1") (pintype "passive"))
      (node (ref "R3") (pin "2") (pinfunction "2_2") (pintype "passive"))
    )
    (net (code "31") (name "Net-(IO_3-3)") (class "Default")
      (node (ref "IO_3") (pin "1") (pinfunction "3_1") (pintype "passive"))
      (node (ref "IO__3") (pin "1") (pinfunction "3_1") (pintype "passive"))
      (node (ref "R4") (pin "2") (pinfunction "2_2") (pintype "passive"))
    )
    (net (code "32") (name "Net-(IO_4-3)") (class "Default")
      (node (ref "IO_4") (pin "1") (pinfunction "3_1") (pintype "passive"))
      (node (ref "IO__4") (pin "1") (pinfunction "3_1") (pintype "passive"))
      (node (ref "R5") (pin "2") (pinfunction "2_2") (pintype "passive"))
    )
    (net (code "33") (name "Net-(IO_5-3)") (class "Default")
      (node (ref "IO_5") (pin "1") (pinfunction "3_1") (pintype "passive"))
      (node (ref "IO__5") (pin "1") (pinfunction "3_1") (pintype "passive"))
      (node (ref "R6") (pin "2") (pinfunction "2_2") (pintype "passive"))
    )
    (net (code "34") (name "Net-(IO_6-3)") (class "Default")
      (node (ref "IO_6") (pin "1") (pinfunction "3_1") (pintype "passive"))
      (node (ref "IO__6") (pin "1") (pinfunction "3_1") (pintype "passive"))
      (node (ref "R7") (pin "2") (pinfunction "2_2") (pintype "passive"))
    )
    (net (code "35") (name "Net-(IO_7-3)") (class "Default")
      (node (ref "IO_7") (pin "1") (pinfunction "3_1") (pintype "passive"))
      (node (ref "IO__7") (pin "1") (pinfunction "3_1") (pintype "passive"))
      (node (ref "R8") (pin "2") (pinfunction "2_2") (pintype "passive"))
    )
    (net (code "36") (name "Net-(IO_8-3)") (class "Default")
      (node (ref "IO_8") (pin "1") (pinfunction "3_1") (pintype "passive"))
      (node (ref "IO__8") (pin "1") (pinfunction "3_1") (pintype "passive"))
      (node (ref "R9") (pin "2") (pinfunction "2_2") (pintype "passive"))
    )
    (net (code "37") (name "Net-(IO_9-3)") (class "Default")
      (node (ref "IO_9") (pin "1") (pinfunction "3_1") (pintype "passive"))
      (node (ref "IO__9") (pin "1") (pinfunction "3_1") (pintype "passive"))
      (node (ref "R10") (pin "2") (pinfunction "2_2") (pintype "passive"))
    )
    (net (code "38") (name "Net-(IO_10-3)") (class "Default")
      (node (ref "IO_10") (pin "1") (pinfunction "3_1") (pintype "passive"))
      (node (ref "IO__10") (pin "1") (pinfunction "3_1") (pintype "passive"))
      (node (ref "R11") (pin "2") (pinfunction "2_2") (pintype "passive"))
    )
    (net (code "39") (name "Net-(IO_11-3)") (class "Default")
      (node (ref "IO_11") (pin "1") (pinfunction "3_1") (pintype "passive"))
      (node (ref "IO__11") (pin "1") (pinfunction "3_1") (pintype "passive"))
      (node (ref "R12") (pin "2") (pinfunction "2_2") (pintype "passive"))
    )
    (net (code "40") (name "Net-(IO_12-3)") (class "Default")
      (node (ref "IO_12") (pin "1") (pinfunction "3_1") (pintype "passive"))
      (node (ref "IO__12") (pin "1") (pinfunction "3_1") (pintype "passive"))
      (node (ref "R13") (pin "2") (pinfunction "2_2") (pintype "passive"))
    )
    (net (code "41") (name "Net-(IO_13-3)") (class "Default")
      (node (ref "IO_13") (pin "1") (pinfunction "3_1") (pintype "passive"))
      (node (ref "IO__13") (pin "1") (pinfunction "3_1") (pintype "passive"))
      (node (ref "R14") (pin "2") (pinfunction "2_2") (pintype "passive"))
    )
    (net (code "42") (name "Net-(IO_14-3)") (class "Default")
      (node (ref "IO_14") (pin "1") (pinfunction "3_1") (pintype "passive"))
      (node (ref "IO__14") (pin "1") (pinfunction "3_1") (pintype "passive"))
      (node (ref "R15") (pin "2") (pinfunction "2_2") (pintype "passive"))
    )
    (net (code "43") (name "Net-(IO_15-3)") (class "Default")
      (node (ref "IO_15") (pin "1") (pinfunction "3_1") (pintype "passive"))
      (node (ref "IO__15") (pin "1") (pinfunction "3_1") (pintype "passive"))
      (node (ref "R16") (pin "2") (pinfunction "2_2") (pintype "passive"))
    )
    (net (code "44") (name "Net-(IO_16-3)") (class "Default")
      (node (ref "IO_16") (pin "1") (pinfunction "3_1") (pintype "passive"))
      (node (ref "IO__16") (pin "1") (pinfunction "3_1") (pintype "passive"))
      (node (ref "R17") (pin "2") (pinfunction "2_2") (pintype "passive"))
    )
    (net (code "45") (name "Net-(IO_17-3)") (class "Default")
      (node (ref "IO_17") (pin "1") (pinfunction "3_1") (pintype "passive"))
      (node (ref "IO__17") (pin "1") (pinfunction "3_1") (pintype "passive"))
      (node (ref "R18") (pin "2") (pinfunction "2_2") (pintype "passive"))
    )
    (net (code "46") (name "Net-(IO_18-3)") (class "Default")
      (node (ref "IO_18") (pin "1") (pinfunction "3_1") (pintype "passive"))
      (node (ref "IO__18") (pin "1") (pinfunction "3_1") (pintype "passive"))
      (node (ref "R19") (pin "2") (pinfunction "2_2") (pintype "passive"))
    )
    (net (code "47") (name "Net-(IO_19-3)") (class "Default")
      (node (ref "IO_19") (pin "1") (pinfunction "3_1") (pintype "passive"))
      (node (ref "IO__19") (pin "1") (pinfunction "3_1") (pintype "passive"))
      (node (ref "R20") (pin "2") (pinfunction "2_2") (pintype "passive"))
    )
    (net (code "48") (name "Net-(MISO-3)") (class "Default")
      (node (ref "MISO") (pin "1") (pinfunction "3_1") (pintype "passive"))
      (node (ref "PIXI_SDO") (pin "1") (pinfunction "3_1") (pintype "passive"))
      (node (ref "TNSY_MISO") (pin "1") (pinfunction "3_1") (pintype "passive"))
    )
    (net (code "49") (name "Net-(MOSI-3)") (class "Default")
      (node (ref "MOSI") (pin "1") (pinfunction "3_1") (pintype "passive"))
      (node (ref "PIXI_SDI") (pin "1") (pinfunction "3_1") (pintype "passive"))
      (node (ref "TNSY_MOSI") (pin "1") (pinfunction "3_1") (pintype "passive"))
    )
    (net (code "50") (name "Net-(PIXI_0-3)") (class "Default")
      (node (ref "PIXI_0") (pin "1") (pinfunction "3_1") (pintype "passive"))
      (node (ref "R1") (pin "1") (pinfunction "1_1") (pintype "passive"))
    )
    (net (code "51") (name "Net-(PIXI_1-3)") (class "Default")
      (node (ref "PIXI_1") (pin "1") (pinfunction "3_1") (pintype "passive"))
      (node (ref "R2") (pin "1") (pinfunction "1_1") (pintype "passive"))
    )
    (net (code "52") (name "Net-(PIXI_2-3)") (class "Default")
      (node (ref "PIXI_2") (pin "1") (pinfunction "3_1") (pintype "passive"))
      (node (ref "R3") (pin "1") (pinfunction "1_1") (pintype "passive"))
    )
    (net (code "53") (name "Net-(PIXI_3-3)") (class "Default")
      (node (ref "PIXI_3") (pin "1") (pinfunction "3_1") (pintype "passive"))
      (node (ref "R4") (pin "1") (pinfunction "1_1") (pintype "passive"))
    )
    (net (code "54") (name "Net-(PIXI_4-3)") (class "Default")
      (node (ref "PIXI_4") (pin "1") (pinfunction "3_1") (pintype "passive"))
      (node (ref "R5") (pin "1") (pinfunction "1_1") (pintype "passive"))
    )
    (net (code "55") (name "Net-(PIXI_5-3)") (class "Default")
      (node (ref "PIXI_5") (pin "1") (pinfunction "3_1") (pintype "passive"))
      (node (ref "R6") (pin "1") (pinfunction "1_1") (pintype "passive"))
    )
    (net (code "56") (name "Net-(PIXI_6-3)") (class "Default")
      (node (ref "PIXI_6") (pin "1") (pinfunction "3_1") (pintype "passive"))
      (node (ref "R7") (pin "1") (pinfunction "1_1") (pintype "passive"))
    )
    (net (code "57") (name "Net-(PIXI_7-3)") (class "Default")
      (node (ref "PIXI_7") (pin "1") (pinfunction "3_1") (pintype "passive"))
      (node (ref "R8") (pin "1") (pinfunction "1_1") (pintype "passive"))
    )
    (net (code "58") (name "Net-(PIXI_8-3)") (class "Default")
      (node (ref "PIXI_8") (pin "1") (pinfunction "3_1") (pintype "passive"))
      (node (ref "R9") (pin "1") (pinfunction "1_1") (pintype "passive"))
    )
    (net (code "59") (name "Net-(PIXI_9-3)") (class "Default")
      (node (ref "PIXI_9") (pin "1") (pinfunction "3_1") (pintype "passive"))
      (node (ref "R10") (pin "1") (pinfunction "1_1") (pintype "passive"))
    )
    (net (code "60") (name "Net-(PIXI_10-3)") (class "Default")
      (node (ref "PIXI_10") (pin "1") (pinfunction "3_1") (pintype "passive"))
      (node (ref "R11") (pin "1") (pinfunction "1_1") (pintype "passive"))
    )
    (net (code "61") (name "Net-(PIXI_11-3)") (class "Default")
      (node (ref "PIXI_11") (pin "1") (pinfunction "3_1") (pintype "passive"))
      (node (ref "R12") (pin "1") (pinfunction "1_1") (pintype "passive"))
    )
    (net (code "62") (name "Net-(PIXI_12-3)") (class "Default")
      (node (ref "PIXI_12") (pin "1") (pinfunction "3_1") (pintype "passive"))
      (node (ref "R13") (pin "1") (pinfunction "1_1") (pintype "passive"))
    )
    (net (code "63") (name "Net-(PIXI_13-3)") (class "Default")
      (node (ref "PIXI_13") (pin "1") (pinfunction "3_1") (pintype "passive"))
      (node (ref "R14") (pin "1") (pinfunction "1_1") (pintype "passive"))
    )
    (net (code "64") (name "Net-(PIXI_14-3)") (class "Default")
      (node (ref "PIXI_14") (pin "1") (pinfunction "3_1") (pintype "passive"))
      (node (ref "R15") (pin "1") (pinfunction "1_1") (pintype "passive"))
    )
    (net (code "65") (name "Net-(PIXI_15-3)") (class "Default")
      (node (ref "PIXI_15") (pin "1") (pinfunction "3_1") (pintype "passive"))
      (node (ref "R16") (pin "1") (pinfunction "1_1") (pintype "passive"))
    )
    (net (code "66") (name "Net-(PIXI_16-3)") (class "Default")
      (node (ref "PIXI_16") (pin "1") (pinfunction "3_1") (pintype "passive"))
      (node (ref "R17") (pin "1") (pinfunction "1_1") (pintype "passive"))
    )
    (net (code "67") (name "Net-(PIXI_17-3)") (class "Default")
      (node (ref "PIXI_17") (pin "1") (pinfunction "3_1") (pintype "passive"))
      (node (ref "R18") (pin "1") (pinfunction "1_1") (pintype "passive"))
    )
    (net (code "68") (name "Net-(PIXI_18-3)") (class "Default")
      (node (ref "PIXI_18") (pin "1") (pinfunction "3_1") (pintype "passive"))
      (node (ref "R19") (pin "1") (pinfunction "1_1") (pintype "passive"))
    )
    (net (code "69") (name "Net-(PIXI_19-3)") (class "Default")
      (node (ref "PIXI_19") (pin "1") (pinfunction "3_1") (pintype "passive"))
      (node (ref "R20") (pin "1") (pinfunction "1_1") (pintype "passive"))
    )
    (net (code "70") (name "Net-(PIXI_CS-3)") (class "Default")
      (node (ref "PIXI_CS") (pin "1") (pinfunction "3_1") (pintype "passive"))
      (node (ref "TNSY_CS") (pin "1") (pinfunction "3_1") (pintype "passive"))
    )
    (net (code "71") (name "Net-(PIXI_SCK-3)") (class "Default")
      (node (ref "PIXI_SCK") (pin "1") (pinfunction "3_1") (pintype "passive"))
      (node (ref "SCK") (pin "1") (pinfunction "3_1") (pintype "passive"))
      (node (ref "TNSY_SCK") (pin "1") (pinfunction "3_1") (pintype "passive"))
    )
    (net (code "72") (name "unconnected-(PIXI_NC1-3-Pad1)") (class "Default")
      (node (ref "PIXI_NC1") (pin "1") (pinfunction "3_1") (pintype "passive"))
    )
    (net (code "73") (name "unconnected-(PIXI_NC2-3-Pad1)") (class "Default")
      (node (ref "PIXI_NC2") (pin "1") (pinfunction "3_1") (pintype "passive"))
    )
    (net (code "74") (name "unconnected-(PIXI_NC3-3-Pad1)") (class "Default")
      (node (ref "PIXI_NC3") (pin "1") (pinfunction "3_1") (pintype "passive"))
    )
    (net (code "75") (name "unconnected-(PIXI_NC4-3-Pad1)") (class "Default")
      (node (ref "PIXI_NC4") (pin "1") (pinfunction "3_1") (pintype "passive"))
    )
    (net (code "76") (name "unconnected-(PIXI_NC5-3-Pad1)") (class "Default")
      (node (ref "PIXI_NC5") (pin "1") (pinfunction "3_1") (pintype "passive"))
    )
    (net (code "77") (name "unconnected-(PIXI_NC6-3-Pad1)") (class "Default")
      (node (ref "PIXI_NC6") (pin "1") (pinfunction "3_1") (pintype "passive"))
    )
    (net (code "78") (name "unconnected-(TNSY_GND2-3-Pad1)") (class "Default")
      (node (ref "TNSY_GND2") (pin "1") (pinfunction "3_1") (pintype "passive"))
    )
  )
)
